# PLCC-RP2350B.net
KiCad netlist of a schematic drawn in Altium Designer
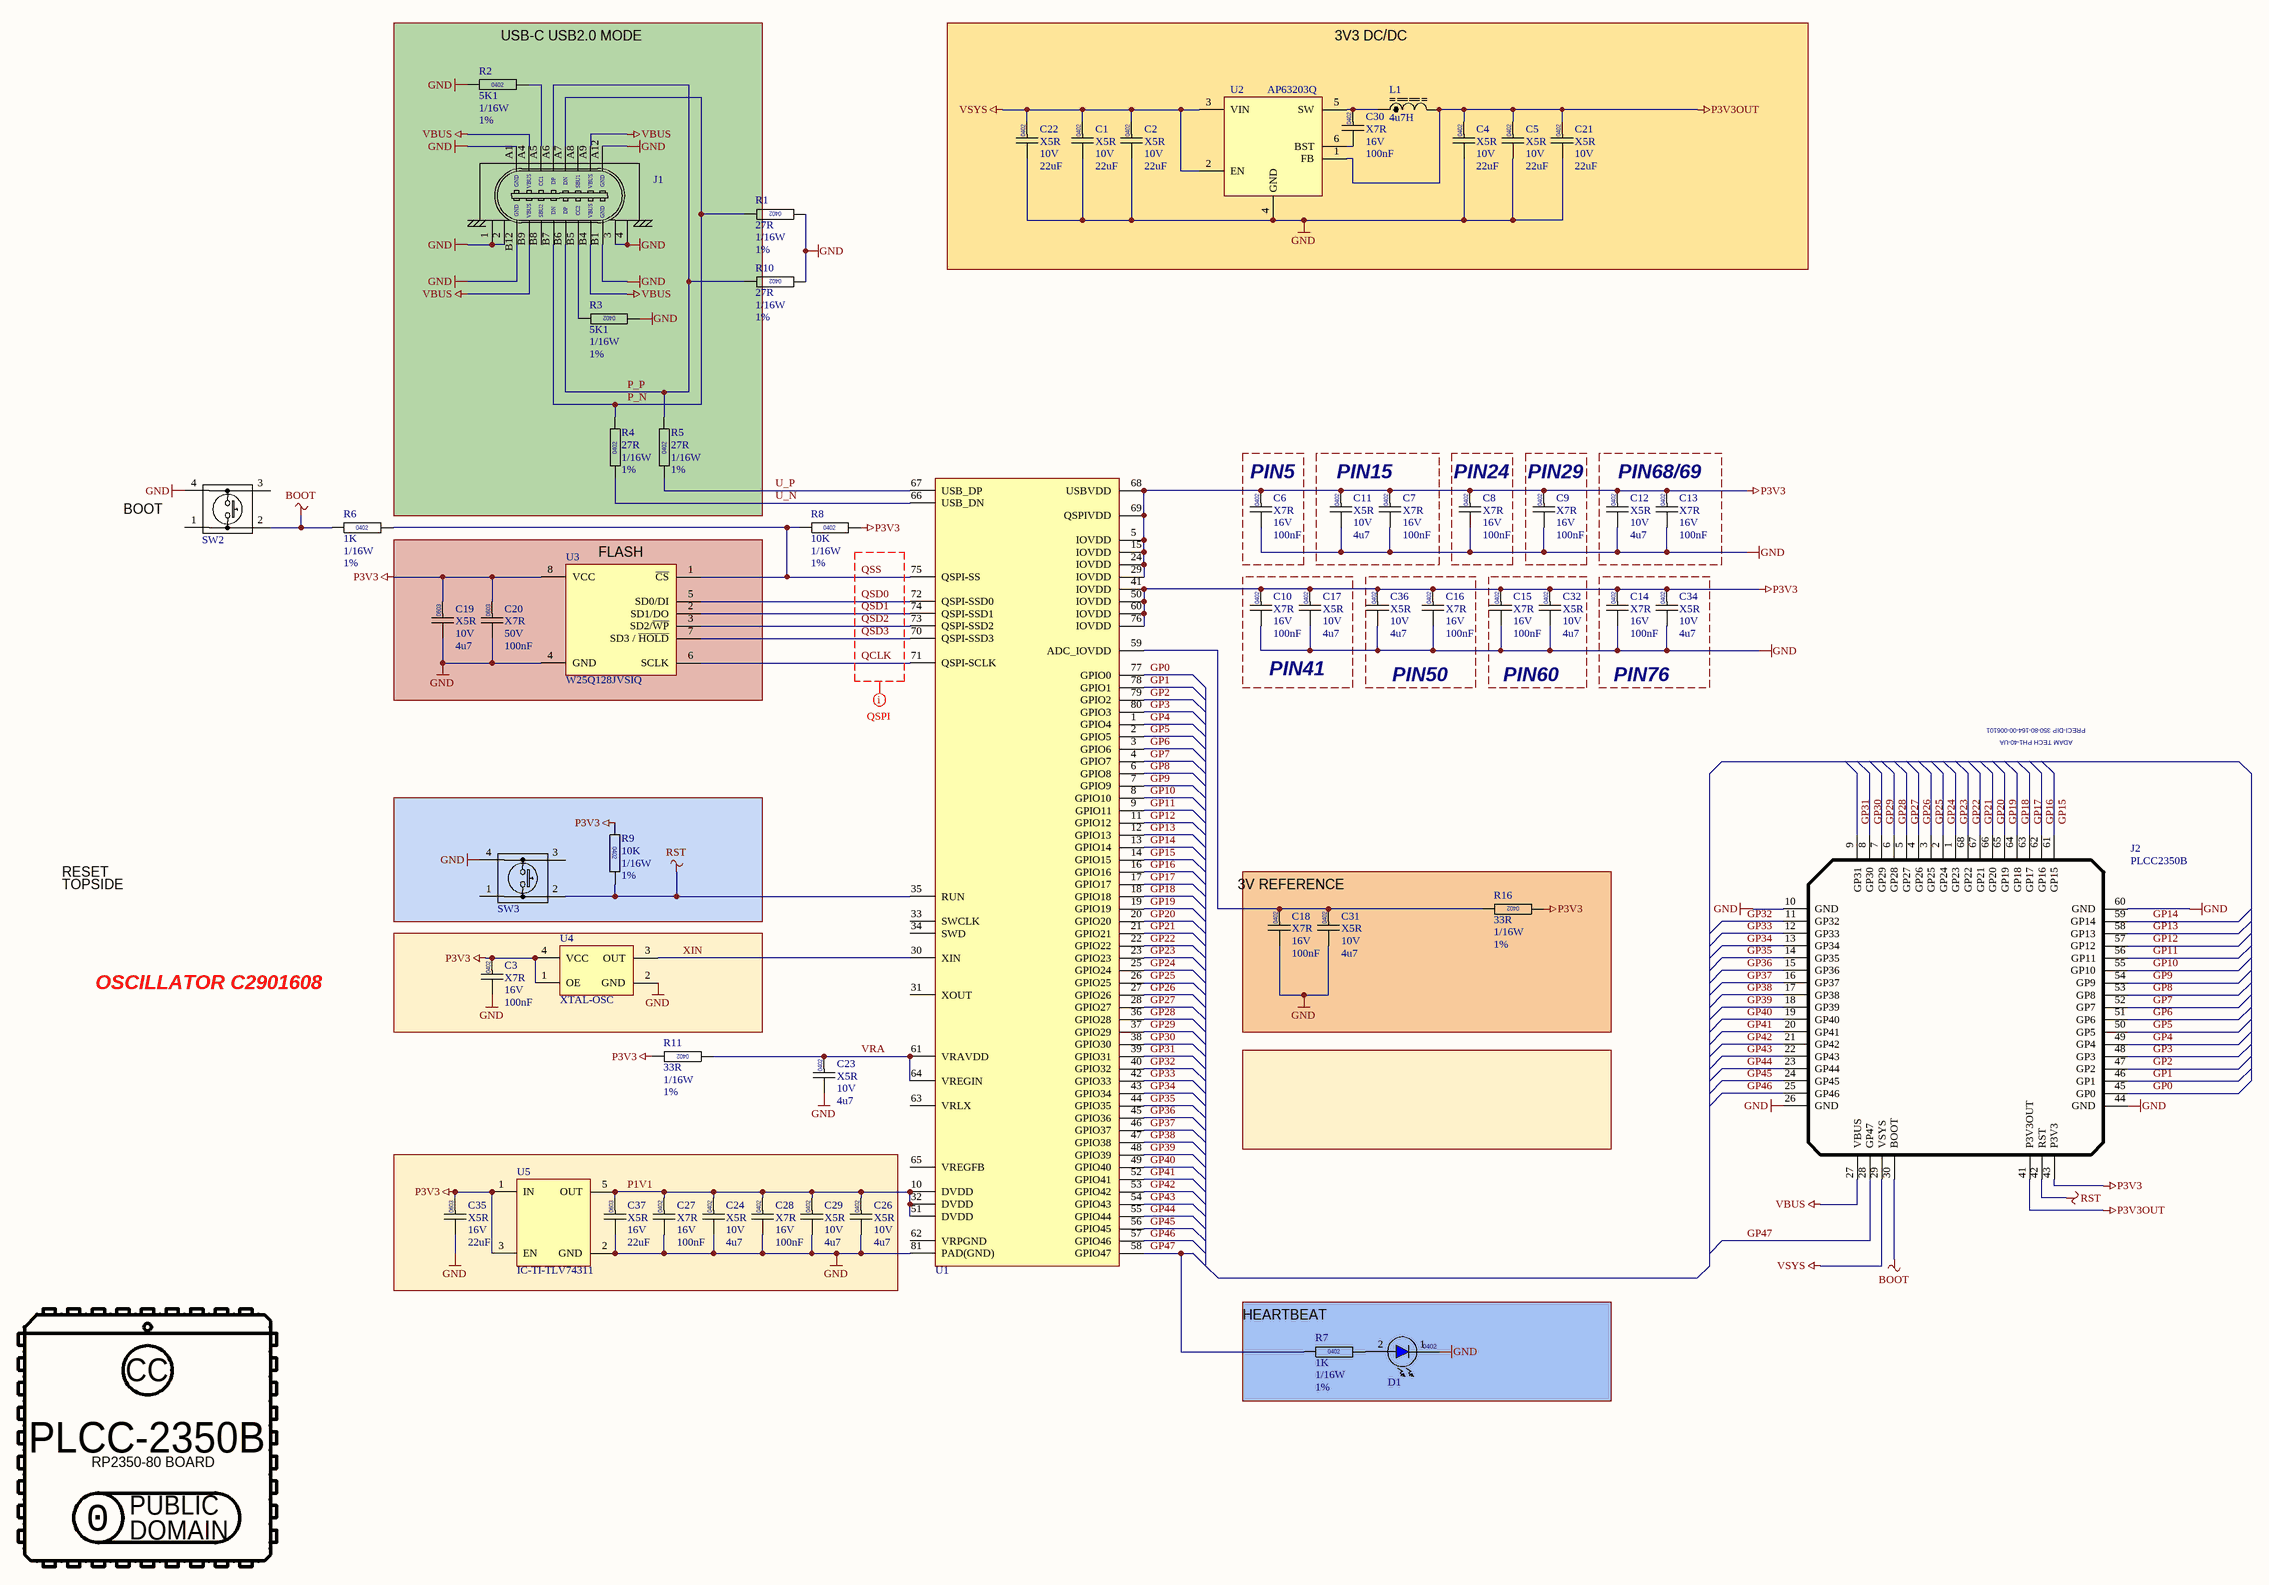
[diagram p0: PLCC-RP2350B.SchDoc]

(export (version "E")
  (design (tool "Eeschema 10.0.6"))
  (components
    (comp (ref "C1")
      (value "CAP0402")
      (footprint "CAPC0402")
      (description "CAPACITOR,CERAMIC,22uF,10V,X5R,0402")
      (fields
        (field (name "DIELECTRIC") "X5R")
        (field (name "VOLTAGE") "10V")
        (field (name "CAPACITANCE") "22uF")
      )
      (libsource (lib "CAPACITORS") (part "CAPC-0402-22uF-10V-X5R"))
    )
    (comp (ref "C2")
      (value "CAP0402")
      (footprint "CAPC0402")
      (description "CAPACITOR,CERAMIC,22uF,10V,X5R,0402")
      (fields
        (field (name "DIELECTRIC") "X5R")
        (field (name "VOLTAGE") "10V")
        (field (name "CAPACITANCE") "22uF")
      )
      (libsource (lib "CAPACITORS") (part "CAPC-0402-22uF-10V-X5R"))
    )
    (comp (ref "C3")
      (value "CAP0402")
      (footprint "CAPC0402")
      (description "CAPACITOR,CERAMIC,100nF,16V,X7R,0402")
      (fields
        (field (name "DIELECTRIC") "X7R")
        (field (name "VOLTAGE") "16V")
        (field (name "CAPACITANCE") "100nF")
      )
      (libsource (lib "CAPACITORS") (part "CAPC-0402-100nF-16V-X7R"))
    )
    (comp (ref "C4")
      (value "CAP0402")
      (footprint "CAPC0402")
      (description "CAPACITOR,CERAMIC,22uF,10V,X5R,0402")
      (fields
        (field (name "DIELECTRIC") "X5R")
        (field (name "VOLTAGE") "10V")
        (field (name "CAPACITANCE") "22uF")
      )
      (libsource (lib "CAPACITORS") (part "CAPC-0402-22uF-10V-X5R"))
    )
    (comp (ref "C5")
      (value "CAP0402")
      (footprint "CAPC0402")
      (description "CAPACITOR,CERAMIC,22uF,10V,X5R,0402")
      (fields
        (field (name "DIELECTRIC") "X5R")
        (field (name "VOLTAGE") "10V")
        (field (name "CAPACITANCE") "22uF")
      )
      (libsource (lib "CAPACITORS") (part "CAPC-0402-22uF-10V-X5R"))
    )
    (comp (ref "C6")
      (value "CAP0402")
      (footprint "CAPC0402")
      (description "CAPACITOR,CERAMIC,100nF,16V,X7R,0402")
      (fields
        (field (name "DIELECTRIC") "X7R")
        (field (name "VOLTAGE") "16V")
        (field (name "CAPACITANCE") "100nF")
      )
      (libsource (lib "CAPACITORS") (part "CAPC-0402-100nF-16V-X7R"))
    )
    (comp (ref "C7")
      (value "CAP0402")
      (footprint "CAPC0402")
      (description "CAPACITOR,CERAMIC,100nF,16V,X7R,0402")
      (fields
        (field (name "DIELECTRIC") "X7R")
        (field (name "VOLTAGE") "16V")
        (field (name "CAPACITANCE") "100nF")
      )
      (libsource (lib "CAPACITORS") (part "CAPC-0402-100nF-16V-X7R"))
    )
    (comp (ref "C8")
      (value "CAP0402")
      (footprint "CAPC0402")
      (description "CAPACITOR,CERAMIC,100nF,16V,X7R,0402")
      (fields
        (field (name "DIELECTRIC") "X7R")
        (field (name "VOLTAGE") "16V")
        (field (name "CAPACITANCE") "100nF")
      )
      (libsource (lib "CAPACITORS") (part "CAPC-0402-100nF-16V-X7R"))
    )
    (comp (ref "C9")
      (value "CAP0402")
      (footprint "CAPC0402")
      (description "CAPACITOR,CERAMIC,100nF,16V,X7R,0402")
      (fields
        (field (name "DIELECTRIC") "X7R")
        (field (name "VOLTAGE") "16V")
        (field (name "CAPACITANCE") "100nF")
      )
      (libsource (lib "CAPACITORS") (part "CAPC-0402-100nF-16V-X7R"))
    )
    (comp (ref "C10")
      (value "CAP0402")
      (footprint "CAPC0402")
      (description "CAPACITOR,CERAMIC,100nF,16V,X7R,0402")
      (fields
        (field (name "DIELECTRIC") "X7R")
        (field (name "VOLTAGE") "16V")
        (field (name "CAPACITANCE") "100nF")
      )
      (libsource (lib "CAPACITORS") (part "CAPC-0402-100nF-16V-X7R"))
    )
    (comp (ref "C11")
      (value "CAP0402")
      (footprint "CAPC0402")
      (description "CAPACITOR,CERAMIC,4u7,10V,X5R,0402")
      (fields
        (field (name "DIELECTRIC") "X5R")
        (field (name "VOLTAGE") "10V")
        (field (name "CAPACITANCE") "4u7")
      )
      (libsource (lib "CAPACITORS") (part "CAPC-0402-4u7-10V-X5R"))
    )
    (comp (ref "C12")
      (value "CAP0402")
      (footprint "CAPC0402")
      (description "CAPACITOR,CERAMIC,4u7,10V,X5R,0402")
      (fields
        (field (name "DIELECTRIC") "X5R")
        (field (name "VOLTAGE") "10V")
        (field (name "CAPACITANCE") "4u7")
      )
      (libsource (lib "CAPACITORS") (part "CAPC-0402-4u7-10V-X5R"))
    )
    (comp (ref "C13")
      (value "CAP0402")
      (footprint "CAPC0402")
      (description "CAPACITOR,CERAMIC,100nF,16V,X7R,0402")
      (fields
        (field (name "DIELECTRIC") "X7R")
        (field (name "VOLTAGE") "16V")
        (field (name "CAPACITANCE") "100nF")
      )
      (libsource (lib "CAPACITORS") (part "CAPC-0402-100nF-16V-X7R"))
    )
    (comp (ref "C14")
      (value "CAP0402")
      (footprint "CAPC0402")
      (description "CAPACITOR,CERAMIC,100nF,16V,X7R,0402")
      (fields
        (field (name "DIELECTRIC") "X7R")
        (field (name "VOLTAGE") "16V")
        (field (name "CAPACITANCE") "100nF")
      )
      (libsource (lib "CAPACITORS") (part "CAPC-0402-100nF-16V-X7R"))
    )
    (comp (ref "C15")
      (value "CAP0402")
      (footprint "CAPC0402")
      (description "CAPACITOR,CERAMIC,100nF,16V,X7R,0402")
      (fields
        (field (name "DIELECTRIC") "X7R")
        (field (name "VOLTAGE") "16V")
        (field (name "CAPACITANCE") "100nF")
      )
      (libsource (lib "CAPACITORS") (part "CAPC-0402-100nF-16V-X7R"))
    )
    (comp (ref "C16")
      (value "CAP0402")
      (footprint "CAPC0402")
      (description "CAPACITOR,CERAMIC,100nF,16V,X7R,0402")
      (fields
        (field (name "DIELECTRIC") "X7R")
        (field (name "VOLTAGE") "16V")
        (field (name "CAPACITANCE") "100nF")
      )
      (libsource (lib "CAPACITORS") (part "CAPC-0402-100nF-16V-X7R"))
    )
    (comp (ref "C17")
      (value "CAP0402")
      (footprint "CAPC0402")
      (description "CAPACITOR,CERAMIC,4u7,10V,X5R,0402")
      (fields
        (field (name "DIELECTRIC") "X5R")
        (field (name "VOLTAGE") "10V")
        (field (name "CAPACITANCE") "4u7")
      )
      (libsource (lib "CAPACITORS") (part "CAPC-0402-4u7-10V-X5R"))
    )
    (comp (ref "C18")
      (value "CAP0402")
      (footprint "CAPC0402")
      (description "CAPACITOR,CERAMIC,100nF,16V,X7R,0402")
      (fields
        (field (name "DIELECTRIC") "X7R")
        (field (name "VOLTAGE") "16V")
        (field (name "CAPACITANCE") "100nF")
      )
      (libsource (lib "CAPACITORS") (part "CAPC-0402-100nF-16V-X7R"))
    )
    (comp (ref "C19")
      (value "CAP0603")
      (footprint "CAPC0603")
      (description "CAPACITOR,CERAMIC,4u7,10V,X5R,0603")
      (fields
        (field (name "DIELECTRIC") "X5R")
        (field (name "VOLTAGE") "10V")
        (field (name "CAPACITANCE") "4u7")
      )
      (libsource (lib "CAPACITORS") (part "CAPC-0603-4u7-10V-X5R"))
    )
    (comp (ref "C20")
      (value "CAP0603")
      (footprint "CAPC0603")
      (description "CAPACITOR,CERAMIC,100nF,50V,X7R,0603")
      (fields
        (field (name "DIELECTRIC") "X7R")
        (field (name "VOLTAGE") "50V")
        (field (name "CAPACITANCE") "100nF")
      )
      (libsource (lib "CAPACITORS") (part "CAPC-0603-100nF-50V-X7R"))
    )
    (comp (ref "C21")
      (value "CAP0402")
      (footprint "CAPC0402")
      (description "CAPACITOR,CERAMIC,22uF,10V,X5R,0402")
      (fields
        (field (name "DIELECTRIC") "X5R")
        (field (name "VOLTAGE") "10V")
        (field (name "CAPACITANCE") "22uF")
      )
      (libsource (lib "CAPACITORS") (part "CAPC-0402-22uF-10V-X5R"))
    )
    (comp (ref "C22")
      (value "CAP0402")
      (footprint "CAPC0402")
      (description "CAPACITOR,CERAMIC,22uF,10V,X5R,0402")
      (fields
        (field (name "DIELECTRIC") "X5R")
        (field (name "VOLTAGE") "10V")
        (field (name "CAPACITANCE") "22uF")
      )
      (libsource (lib "CAPACITORS") (part "CAPC-0402-22uF-10V-X5R"))
    )
    (comp (ref "C23")
      (value "CAP0402")
      (footprint "CAPC0402")
      (description "CAPACITOR,CERAMIC,4u7,10V,X5R,0402")
      (fields
        (field (name "DIELECTRIC") "X5R")
        (field (name "VOLTAGE") "10V")
        (field (name "CAPACITANCE") "4u7")
      )
      (libsource (lib "CAPACITORS") (part "CAPC-0402-4u7-10V-X5R"))
    )
    (comp (ref "C24")
      (value "CAP0402")
      (footprint "CAPC0402")
      (description "CAPACITOR,CERAMIC,4u7,10V,X5R,0402")
      (fields
        (field (name "DIELECTRIC") "X5R")
        (field (name "VOLTAGE") "10V")
        (field (name "CAPACITANCE") "4u7")
      )
      (libsource (lib "CAPACITORS") (part "CAPC-0402-4u7-10V-X5R"))
    )
    (comp (ref "C26")
      (value "CAP0402")
      (footprint "CAPC0402")
      (description "CAPACITOR,CERAMIC,4u7,10V,X5R,0402")
      (fields
        (field (name "DIELECTRIC") "X5R")
        (field (name "VOLTAGE") "10V")
        (field (name "CAPACITANCE") "4u7")
      )
      (libsource (lib "CAPACITORS") (part "CAPC-0402-4u7-10V-X5R"))
    )
    (comp (ref "C27")
      (value "CAP0402")
      (footprint "CAPC0402")
      (description "CAPACITOR,CERAMIC,100nF,16V,X7R,0402")
      (fields
        (field (name "DIELECTRIC") "X7R")
        (field (name "VOLTAGE") "16V")
        (field (name "CAPACITANCE") "100nF")
      )
      (libsource (lib "CAPACITORS") (part "CAPC-0402-100nF-16V-X7R"))
    )
    (comp (ref "C28")
      (value "CAP0402")
      (footprint "CAPC0402")
      (description "CAPACITOR,CERAMIC,100nF,16V,X7R,0402")
      (fields
        (field (name "DIELECTRIC") "X7R")
        (field (name "VOLTAGE") "16V")
        (field (name "CAPACITANCE") "100nF")
      )
      (libsource (lib "CAPACITORS") (part "CAPC-0402-100nF-16V-X7R"))
    )
    (comp (ref "C29")
      (value "CAP0402")
      (footprint "CAPC0402")
      (description "CAPACITOR,CERAMIC,4u7,10V,X5R,0402")
      (fields
        (field (name "DIELECTRIC") "X5R")
        (field (name "VOLTAGE") "10V")
        (field (name "CAPACITANCE") "4u7")
      )
      (libsource (lib "CAPACITORS") (part "CAPC-0402-4u7-10V-X5R"))
    )
    (comp (ref "C30")
      (value "CAP0402")
      (footprint "CAPC0402")
      (description "CAPACITOR,CERAMIC,100nF,16V,X7R,0402")
      (fields
        (field (name "DIELECTRIC") "X7R")
        (field (name "VOLTAGE") "16V")
        (field (name "CAPACITANCE") "100nF")
      )
      (libsource (lib "CAPACITORS") (part "CAPC-0402-100nF-16V-X7R"))
    )
    (comp (ref "C31")
      (value "CAP0402")
      (footprint "CAPC0402")
      (description "CAPACITOR,CERAMIC,4u7,10V,X5R,0402")
      (fields
        (field (name "DIELECTRIC") "X5R")
        (field (name "VOLTAGE") "10V")
        (field (name "CAPACITANCE") "4u7")
      )
      (libsource (lib "CAPACITORS") (part "CAPC-0402-4u7-10V-X5R"))
    )
    (comp (ref "C32")
      (value "CAP0402")
      (footprint "CAPC0402")
      (description "CAPACITOR,CERAMIC,4u7,10V,X5R,0402")
      (fields
        (field (name "DIELECTRIC") "X5R")
        (field (name "VOLTAGE") "10V")
        (field (name "CAPACITANCE") "4u7")
      )
      (libsource (lib "CAPACITORS") (part "CAPC-0402-4u7-10V-X5R"))
    )
    (comp (ref "C34")
      (value "CAP0402")
      (footprint "CAPC0402")
      (description "CAPACITOR,CERAMIC,4u7,10V,X5R,0402")
      (fields
        (field (name "DIELECTRIC") "X5R")
        (field (name "VOLTAGE") "10V")
        (field (name "CAPACITANCE") "4u7")
      )
      (libsource (lib "CAPACITORS") (part "CAPC-0402-4u7-10V-X5R"))
    )
    (comp (ref "C35")
      (value "CAP0603")
      (footprint "CAPC0603")
      (description "CAPACITOR,CERAMIC,22uF,16V,X5R,0603")
      (fields
        (field (name "DIELECTRIC") "X5R")
        (field (name "VOLTAGE") "16V")
        (field (name "CAPACITANCE") "22uF")
      )
      (libsource (lib "CAPACITORS") (part "CAPC-0603-22uF-16V-X5R"))
    )
    (comp (ref "C36")
      (value "CAP0402")
      (footprint "CAPC0402")
      (description "CAPACITOR,CERAMIC,4u7,10V,X5R,0402")
      (fields
        (field (name "DIELECTRIC") "X5R")
        (field (name "VOLTAGE") "10V")
        (field (name "CAPACITANCE") "4u7")
      )
      (libsource (lib "CAPACITORS") (part "CAPC-0402-4u7-10V-X5R"))
    )
    (comp (ref "C37")
      (value "CAP0603")
      (footprint "CAPC0603")
      (description "CAPACITOR,CERAMIC,22uF,16V,X5R,0603")
      (fields
        (field (name "DIELECTRIC") "X5R")
        (field (name "VOLTAGE") "16V")
        (field (name "CAPACITANCE") "22uF")
      )
      (libsource (lib "CAPACITORS") (part "CAPC-0603-22uF-16V-X5R"))
    )
    (comp (ref "D1")
      (value "LED-0402-BLUE")
      (footprint "LED-0402-BLUE")
      (description "LED,SMD,BLUE,90mCd,0603")
      (libsource (lib "LED") (part "LED-0402-BLUE"))
    )
    (comp (ref "J1")
      (value "CONN-USBC-USB2-HOR")
      (footprint "CONN-GCT-USB4085")
      (description "CONN,USB-C,16P,RA,TH,8.94X9.17")
      (libsource (lib "CONNECTORS") (part "CONN-USBC-USB2-HOR"))
    )
    (comp (ref "J2")
      (value "PLCC2350B")
      (footprint "PLCC2350B")
      (libsource (lib "PLCC-RP2350B") (part "PLCC2350B"))
    )
    (comp (ref "L1")
      (value "4u7H")
      (footprint "IND-ABRACON-ASPI-3012S-3R9N-T")
      (description "IND,4.7uH,1.06A,3X3, NRH3012T4R7MN")
      (fields (field (name "Comment") "4.7uH"))
      (libsource (lib "INDUCTORS") (part "IND-TAIYO-NRH3012T4R7MN"))
    )
    (comp (ref "LOGO1")
      (value "LOGO-LICENSE-CC0-PUBLIC")
      (footprint "LOGO-LICENSE-CC0-PUBLIC")
      (libsource (lib "LOGO") (part "LOGO-LICENSE-CC0-PUBLIC"))
    )
    (comp (ref "LOGO2")
      (value "LOGO-LICENSE-CC")
      (footprint "LOGO-LICENSE-CC")
      (libsource (lib "LOGO") (part "LOGO-LICENSE-CC"))
    )
    (comp (ref "R1")
      (value "27R")
      (footprint "RESC0402")
      (description "RESISTOR,27R,1%,63mW,0402 (1005)")
      (fields
        (field (name "POWER") "1/16W")
        (field (name "TOLERANCE") "1%")
        (field (name "Comment") "RESC0402")
      )
      (libsource (lib "RESISTORS") (part "RESC-0402-27R-1%-1/10W"))
    )
    (comp (ref "R2")
      (value "5K1")
      (footprint "RESC0402")
      (description "RESISTOR,5K1,1%,63mW,0402 (1005)")
      (fields
        (field (name "POWER") "1/16W")
        (field (name "TOLERANCE") "1%")
        (field (name "Comment") "RESC0402")
      )
      (libsource (lib "RESISTORS") (part "RESC-0402-5K1-1%-1/10W"))
    )
    (comp (ref "R3")
      (value "5K1")
      (footprint "RESC0402")
      (description "RESISTOR,5K1,1%,63mW,0402 (1005)")
      (fields
        (field (name "POWER") "1/16W")
        (field (name "TOLERANCE") "1%")
        (field (name "Comment") "RESC0402")
      )
      (libsource (lib "RESISTORS") (part "RESC-0402-5K1-1%-1/10W"))
    )
    (comp (ref "R4")
      (value "27R")
      (footprint "RESC0402")
      (description "RESISTOR,27R,1%,63mW,0402 (1005)")
      (fields
        (field (name "POWER") "1/16W")
        (field (name "TOLERANCE") "1%")
        (field (name "Comment") "RESC0402")
      )
      (libsource (lib "RESISTORS") (part "RESC-0402-27R-1%-1/10W"))
    )
    (comp (ref "R5")
      (value "27R")
      (footprint "RESC0402")
      (description "RESISTOR,27R,1%,63mW,0402 (1005)")
      (fields
        (field (name "POWER") "1/16W")
        (field (name "TOLERANCE") "1%")
        (field (name "Comment") "RESC0402")
      )
      (libsource (lib "RESISTORS") (part "RESC-0402-27R-1%-1/10W"))
    )
    (comp (ref "R6")
      (value "1K")
      (footprint "RESC0402")
      (description "RESISTOR,1K,1%,63mW,0402 (1005)")
      (fields
        (field (name "POWER") "1/16W")
        (field (name "TOLERANCE") "1%")
        (field (name "Comment") "RESC0402")
      )
      (libsource (lib "RESISTORS") (part "RESC-0402-1K-1%-1/10W"))
    )
    (comp (ref "R7")
      (value "1K")
      (footprint "RESC0402")
      (description "RESISTOR,1K,1%,63mW,0402 (1005)")
      (fields
        (field (name "POWER") "1/16W")
        (field (name "TOLERANCE") "1%")
        (field (name "Comment") "RESC0402")
      )
      (libsource (lib "RESISTORS") (part "RESC-0402-1K-1%-1/10W"))
    )
    (comp (ref "R8")
      (value "10K")
      (footprint "RESC0402")
      (description "RESISTOR,10K,1%,63mW,0402 (1005)")
      (fields
        (field (name "POWER") "1/16W")
        (field (name "TOLERANCE") "1%")
        (field (name "Comment") "RESC0402")
      )
      (libsource (lib "RESISTORS") (part "RESC-0402-10K-1%-1/10W"))
    )
    (comp (ref "R9")
      (value "10K")
      (footprint "RESC0402")
      (description "RESISTOR,10K,1%,63mW,0402 (1005)")
      (fields
        (field (name "POWER") "1/16W")
        (field (name "TOLERANCE") "1%")
        (field (name "Comment") "RESC0402")
      )
      (libsource (lib "RESISTORS") (part "RESC-0402-10K-1%-1/10W"))
    )
    (comp (ref "R10")
      (value "27R")
      (footprint "RESC0402")
      (description "RESISTOR,27R,1%,63mW,0402 (1005)")
      (fields
        (field (name "POWER") "1/16W")
        (field (name "TOLERANCE") "1%")
        (field (name "Comment") "RESC0402")
      )
      (libsource (lib "RESISTORS") (part "RESC-0402-27R-1%-1/10W"))
    )
    (comp (ref "R11")
      (value "33R")
      (footprint "RESC0402")
      (description "RESISTOR,33R,1%,63mW,0402 (1005)")
      (fields
        (field (name "POWER") "1/16W")
        (field (name "TOLERANCE") "1%")
        (field (name "Comment") "RESC0402")
      )
      (libsource (lib "RESISTORS") (part "RESC-0402-33R-1%-1/10W"))
    )
    (comp (ref "R16")
      (value "33R")
      (footprint "RESC0402")
      (description "RESISTOR,33R,1%,63mW,0402 (1005)")
      (fields
        (field (name "POWER") "1/16W")
        (field (name "TOLERANCE") "1%")
        (field (name "Comment") "RESC0402")
      )
      (libsource (lib "RESISTORS") (part "RESC-0402-33R-1%-1/10W"))
    )
    (comp (ref "SW2")
      (value "SWITCH-PANASONIC-EVP-AA202K")
      (footprint "SWITCH-PANASONIC-EVP-AA202K")
      (description "SW,SMD,TACT,4PIN,2.9X3.5,4PIN")
      (libsource (lib "SWITCH") (part "SWITCH-PANASONIC-EVP-AA202K"))
    )
    (comp (ref "SW3")
      (value "SWITCH-PANASONIC-EVP-AA202K")
      (footprint "SWITCH-PANASONIC-EVP-AA202K")
      (description "SW,SMD,TACT,4PIN,2.9X3.5,4PIN")
      (libsource (lib "SWITCH") (part "SWITCH-PANASONIC-EVP-AA202K"))
    )
    (comp (ref "U1")
      (value "IC-RP2350-DIP64")
      (footprint "QFN40P1000X1000X90_HS-81N")
      (description "IC,CPU,RP2350B,QFN80")
      (libsource (lib "IC-CPU") (part "IC-RP2350-DIP64"))
    )
    (comp (ref "U2")
      (value "AP63203Q")
      (footprint "SOT23-6")
      (description "IC,PMIC,STEP-DOWN, 2A 3.3V")
      (libsource (lib "IC-REG") (part "IC-DIODES-AP63203Q"))
    )
    (comp (ref "U3")
      (value "W25Q128JVSIQ")
      (footprint "SO127P790-8N")
      (description "IC,FLASH,QSPI,16Mx8")
      (libsource (lib "IC-SPI") (part "IC-WINBOND-W25Q128JVSIQ"))
    )
    (comp (ref "U4")
      (value "XTAL-OSC")
      (footprint "XOSC-SCTF-SX1M12.000M10F30TNN")
      (libsource (lib "PLCC-RP2350B") (part "XTAL-OSC"))
    )
    (comp (ref "U5")
      (value "IC-TI-TLV74311")
      (footprint "SOT23-5")
      (libsource (lib "PLCC-RP2350B") (part "IC-TI-TLV74311"))
    )
  )
  (nets
    (net (code "1") (name "/GP0") (class "Default")
      (node (ref "J2") (pin "45") (pinfunction "GP0_45") (pintype "passive"))
      (node (ref "U1") (pin "77") (pinfunction "GPIO0_77") (pintype "passive"))
    )
    (net (code "2") (name "/GP1") (class "Default")
      (node (ref "J2") (pin "46") (pinfunction "GP1_46") (pintype "passive"))
      (node (ref "U1") (pin "78") (pinfunction "GPIO1_78") (pintype "passive"))
    )
    (net (code "3") (name "/GP2") (class "Default")
      (node (ref "J2") (pin "47") (pinfunction "GP2_47") (pintype "passive"))
      (node (ref "U1") (pin "79") (pinfunction "GPIO2_79") (pintype "passive"))
    )
    (net (code "4") (name "/GP3") (class "Default")
      (node (ref "J2") (pin "48") (pinfunction "GP3_48") (pintype "passive"))
      (node (ref "U1") (pin "80") (pinfunction "GPIO3_80") (pintype "passive"))
    )
    (net (code "5") (name "/GP4") (class "Default")
      (node (ref "J2") (pin "49") (pinfunction "GP4_49") (pintype "passive"))
      (node (ref "U1") (pin "1") (pinfunction "GPIO4_1") (pintype "passive"))
    )
    (net (code "6") (name "/GP5") (class "Default")
      (node (ref "J2") (pin "50") (pinfunction "GP5_50") (pintype "passive"))
      (node (ref "U1") (pin "2") (pinfunction "GPIO5_2") (pintype "passive"))
    )
    (net (code "7") (name "/GP6") (class "Default")
      (node (ref "J2") (pin "51") (pinfunction "GP6_51") (pintype "passive"))
      (node (ref "U1") (pin "3") (pinfunction "GPIO6_3") (pintype "passive"))
    )
    (net (code "8") (name "/GP7") (class "Default")
      (node (ref "J2") (pin "52") (pinfunction "GP7_52") (pintype "passive"))
      (node (ref "U1") (pin "4") (pinfunction "GPIO7_4") (pintype "passive"))
    )
    (net (code "9") (name "/GP8") (class "Default")
      (node (ref "J2") (pin "53") (pinfunction "GP8_53") (pintype "passive"))
      (node (ref "U1") (pin "6") (pinfunction "GPIO8_6") (pintype "passive"))
    )
    (net (code "10") (name "/GP9") (class "Default")
      (node (ref "J2") (pin "54") (pinfunction "GP9_54") (pintype "passive"))
      (node (ref "U1") (pin "7") (pinfunction "GPIO9_7") (pintype "passive"))
    )
    (net (code "11") (name "/GP10") (class "Default")
      (node (ref "J2") (pin "55") (pinfunction "GP10_55") (pintype "passive"))
      (node (ref "U1") (pin "8") (pinfunction "GPIO10_8") (pintype "passive"))
    )
    (net (code "12") (name "/GP11") (class "Default")
      (node (ref "J2") (pin "56") (pinfunction "GP11_56") (pintype "passive"))
      (node (ref "U1") (pin "9") (pinfunction "GPIO11_9") (pintype "passive"))
    )
    (net (code "13") (name "/GP12") (class "Default")
      (node (ref "J2") (pin "57") (pinfunction "GP12_57") (pintype "passive"))
      (node (ref "U1") (pin "11") (pinfunction "GPIO12_11") (pintype "passive"))
    )
    (net (code "14") (name "/GP13") (class "Default")
      (node (ref "J2") (pin "58") (pinfunction "GP13_58") (pintype "passive"))
      (node (ref "U1") (pin "12") (pinfunction "GPIO13_12") (pintype "passive"))
    )
    (net (code "15") (name "/GP14") (class "Default")
      (node (ref "J2") (pin "59") (pinfunction "GP14_59") (pintype "passive"))
      (node (ref "U1") (pin "13") (pinfunction "GPIO14_13") (pintype "passive"))
    )
    (net (code "16") (name "/GP15") (class "Default")
      (node (ref "J2") (pin "61") (pinfunction "GP15_61") (pintype "passive"))
      (node (ref "U1") (pin "14") (pinfunction "GPIO15_14") (pintype "passive"))
    )
    (net (code "17") (name "/GP16") (class "Default")
      (node (ref "J2") (pin "62") (pinfunction "GP16_62") (pintype "passive"))
      (node (ref "U1") (pin "16") (pinfunction "GPIO16_16") (pintype "passive"))
    )
    (net (code "18") (name "/GP17") (class "Default")
      (node (ref "J2") (pin "63") (pinfunction "GP17_63") (pintype "passive"))
      (node (ref "U1") (pin "17") (pinfunction "GPIO17_17") (pintype "passive"))
    )
    (net (code "19") (name "/GP18") (class "Default")
      (node (ref "J2") (pin "64") (pinfunction "GP18_64") (pintype "passive"))
      (node (ref "U1") (pin "18") (pinfunction "GPIO18_18") (pintype "passive"))
    )
    (net (code "20") (name "/GP19") (class "Default")
      (node (ref "J2") (pin "65") (pinfunction "GP19_65") (pintype "passive"))
      (node (ref "U1") (pin "19") (pinfunction "GPIO19_19") (pintype "passive"))
    )
    (net (code "21") (name "/GP20") (class "Default")
      (node (ref "J2") (pin "66") (pinfunction "GP20_66") (pintype "passive"))
      (node (ref "U1") (pin "20") (pinfunction "GPIO20_20") (pintype "passive"))
    )
    (net (code "22") (name "/GP21") (class "Default")
      (node (ref "J2") (pin "67") (pinfunction "GP21_67") (pintype "passive"))
      (node (ref "U1") (pin "21") (pinfunction "GPIO21_21") (pintype "passive"))
    )
    (net (code "23") (name "/GP22") (class "Default")
      (node (ref "J2") (pin "68") (pinfunction "GP22_68") (pintype "passive"))
      (node (ref "U1") (pin "22") (pinfunction "GPIO22_22") (pintype "passive"))
    )
    (net (code "24") (name "/GP23") (class "Default")
      (node (ref "J2") (pin "1") (pinfunction "GP23_1") (pintype "passive"))
      (node (ref "U1") (pin "23") (pinfunction "GPIO23_23") (pintype "passive"))
    )
    (net (code "25") (name "/GP24") (class "Default")
      (node (ref "J2") (pin "2") (pinfunction "GP24_2") (pintype "passive"))
      (node (ref "U1") (pin "25") (pinfunction "GPIO24_25") (pintype "passive"))
    )
    (net (code "26") (name "/GP25") (class "Default")
      (node (ref "J2") (pin "3") (pinfunction "GP25_3") (pintype "passive"))
      (node (ref "U1") (pin "26") (pinfunction "GPIO25_26") (pintype "passive"))
    )
    (net (code "27") (name "/GP26") (class "Default")
      (node (ref "J2") (pin "4") (pinfunction "GP26_4") (pintype "passive"))
      (node (ref "U1") (pin "27") (pinfunction "GPIO26_27") (pintype "passive"))
    )
    (net (code "28") (name "/GP27") (class "Default")
      (node (ref "J2") (pin "5") (pinfunction "GP27_5") (pintype "passive"))
      (node (ref "U1") (pin "28") (pinfunction "GPIO27_28") (pintype "passive"))
    )
    (net (code "29") (name "/GP28") (class "Default")
      (node (ref "J2") (pin "6") (pinfunction "GP28_6") (pintype "passive"))
      (node (ref "U1") (pin "36") (pinfunction "GPIO28_36") (pintype "passive"))
    )
    (net (code "30") (name "/GP29") (class "Default")
      (node (ref "J2") (pin "7") (pinfunction "GP29_7") (pintype "passive"))
      (node (ref "U1") (pin "37") (pinfunction "GPIO29_37") (pintype "passive"))
    )
    (net (code "31") (name "/GP30") (class "Default")
      (node (ref "J2") (pin "8") (pinfunction "GP30_8") (pintype "passive"))
      (node (ref "U1") (pin "38") (pinfunction "GPIO30_38") (pintype "passive"))
    )
    (net (code "32") (name "/GP31") (class "Default")
      (node (ref "J2") (pin "9") (pinfunction "GP31_9") (pintype "passive"))
      (node (ref "U1") (pin "39") (pinfunction "GPIO31_39") (pintype "passive"))
    )
    (net (code "33") (name "/GP32") (class "Default")
      (node (ref "J2") (pin "11") (pinfunction "GP32_11") (pintype "passive"))
      (node (ref "U1") (pin "40") (pinfunction "GPIO32_40") (pintype "passive"))
    )
    (net (code "34") (name "/GP33") (class "Default")
      (node (ref "J2") (pin "12") (pinfunction "GP33_12") (pintype "passive"))
      (node (ref "U1") (pin "42") (pinfunction "GPIO33_42") (pintype "passive"))
    )
    (net (code "35") (name "/GP34") (class "Default")
      (node (ref "J2") (pin "13") (pinfunction "GP34_13") (pintype "passive"))
      (node (ref "U1") (pin "43") (pinfunction "GPIO34_43") (pintype "passive"))
    )
    (net (code "36") (name "/GP35") (class "Default")
      (node (ref "J2") (pin "14") (pinfunction "GP35_14") (pintype "passive"))
      (node (ref "U1") (pin "44") (pinfunction "GPIO35_44") (pintype "passive"))
    )
    (net (code "37") (name "/GP36") (class "Default")
      (node (ref "J2") (pin "15") (pinfunction "GP36_15") (pintype "passive"))
      (node (ref "U1") (pin "45") (pinfunction "GPIO36_45") (pintype "passive"))
    )
    (net (code "38") (name "/GP37") (class "Default")
      (node (ref "J2") (pin "16") (pinfunction "GP37_16") (pintype "passive"))
      (node (ref "U1") (pin "46") (pinfunction "GPIO37_46") (pintype "passive"))
    )
    (net (code "39") (name "/GP38") (class "Default")
      (node (ref "J2") (pin "17") (pinfunction "GP38_17") (pintype "passive"))
      (node (ref "U1") (pin "47") (pinfunction "GPIO38_47") (pintype "passive"))
    )
    (net (code "40") (name "/GP39") (class "Default")
      (node (ref "J2") (pin "18") (pinfunction "GP39_18") (pintype "passive"))
      (node (ref "U1") (pin "48") (pinfunction "GPIO39_48") (pintype "passive"))
    )
    (net (code "41") (name "/GP40") (class "Default")
      (node (ref "J2") (pin "19") (pinfunction "GP40_19") (pintype "passive"))
      (node (ref "U1") (pin "49") (pinfunction "GPIO40_49") (pintype "passive"))
    )
    (net (code "42") (name "/GP41") (class "Default")
      (node (ref "J2") (pin "20") (pinfunction "GP41_20") (pintype "passive"))
      (node (ref "U1") (pin "52") (pinfunction "GPIO41_52") (pintype "passive"))
    )
    (net (code "43") (name "/GP42") (class "Default")
      (node (ref "J2") (pin "21") (pinfunction "GP42_21") (pintype "passive"))
      (node (ref "U1") (pin "53") (pinfunction "GPIO42_53") (pintype "passive"))
    )
    (net (code "44") (name "/GP43") (class "Default")
      (node (ref "J2") (pin "22") (pinfunction "GP43_22") (pintype "passive"))
      (node (ref "U1") (pin "54") (pinfunction "GPIO43_54") (pintype "passive"))
    )
    (net (code "45") (name "/GP44") (class "Default")
      (node (ref "J2") (pin "23") (pinfunction "GP44_23") (pintype "passive"))
      (node (ref "U1") (pin "55") (pinfunction "GPIO44_55") (pintype "passive"))
    )
    (net (code "46") (name "/GP45") (class "Default")
      (node (ref "J2") (pin "24") (pinfunction "GP45_24") (pintype "passive"))
      (node (ref "U1") (pin "56") (pinfunction "GPIO45_56") (pintype "passive"))
    )
    (net (code "47") (name "/GP46") (class "Default")
      (node (ref "J2") (pin "25") (pinfunction "GP46_25") (pintype "passive"))
      (node (ref "U1") (pin "57") (pinfunction "GPIO46_57") (pintype "passive"))
    )
    (net (code "48") (name "/GP47") (class "Default")
      (node (ref "J2") (pin "28") (pinfunction "GP47_28") (pintype "passive"))
      (node (ref "R7") (pin "1") (pintype "passive"))
      (node (ref "U1") (pin "58") (pinfunction "GPIO47_58") (pintype "passive"))
    )
    (net (code "49") (name "/P1V1") (class "Default")
      (node (ref "C24") (pin "1") (pintype "passive"))
      (node (ref "C26") (pin "1") (pintype "passive"))
      (node (ref "C27") (pin "1") (pintype "passive"))
      (node (ref "C28") (pin "1") (pintype "passive"))
      (node (ref "C29") (pin "1") (pintype "passive"))
      (node (ref "C37") (pin "1") (pintype "passive"))
      (node (ref "U1") (pin "10") (pinfunction "DVDD_10") (pintype "passive"))
      (node (ref "U1") (pin "32") (pinfunction "DVDD_32") (pintype "passive"))
      (node (ref "U1") (pin "51") (pinfunction "DVDD_51") (pintype "passive"))
      (node (ref "U5") (pin "5") (pinfunction "OUT_5") (pintype "passive"))
    )
    (net (code "50") (name "/P_N") (class "Default")
      (node (ref "J1") (pin "A7") (pinfunction "A7_A7") (pintype "passive"))
      (node (ref "J1") (pin "B7") (pinfunction "B7_B7") (pintype "passive"))
      (node (ref "R1") (pin "1") (pintype "passive"))
      (node (ref "R4") (pin "1") (pintype "passive"))
    )
    (net (code "51") (name "/P_P") (class "Default")
      (node (ref "J1") (pin "A6") (pinfunction "A6_A6") (pintype "passive"))
      (node (ref "J1") (pin "B6") (pinfunction "B6_B6") (pintype "passive"))
      (node (ref "R10") (pin "1") (pintype "passive"))
      (node (ref "R5") (pin "1") (pintype "passive"))
    )
    (net (code "52") (name "/QCLK") (class "Default")
      (node (ref "U1") (pin "71") (pinfunction "QSPI-SCLK_71") (pintype "passive"))
      (node (ref "U3") (pin "6") (pinfunction "SCLK_6") (pintype "passive"))
    )
    (net (code "53") (name "/QSD0") (class "Default")
      (node (ref "U1") (pin "72") (pinfunction "QSPI-SSD0_72") (pintype "passive"))
      (node (ref "U3") (pin "5") (pinfunction "SD0/DI_5") (pintype "passive"))
    )
    (net (code "54") (name "/QSD1") (class "Default")
      (node (ref "U1") (pin "74") (pinfunction "QSPI-SSD1_74") (pintype "passive"))
      (node (ref "U3") (pin "2") (pinfunction "SD1/DO_2") (pintype "passive"))
    )
    (net (code "55") (name "/QSD2") (class "Default")
      (node (ref "U1") (pin "73") (pinfunction "QSPI-SSD2_73") (pintype "passive"))
      (node (ref "U3") (pin "3") (pinfunction "SD2/~{WP}_3") (pintype "passive"))
    )
    (net (code "56") (name "/QSD3") (class "Default")
      (node (ref "U1") (pin "70") (pinfunction "QSPI-SSD3_70") (pintype "passive"))
      (node (ref "U3") (pin "7") (pinfunction "SD3_/_~{HOLD}_7") (pintype "passive"))
    )
    (net (code "57") (name "/QSS") (class "Default")
      (node (ref "R6") (pin "2") (pintype "passive"))
      (node (ref "R8") (pin "1") (pintype "passive"))
      (node (ref "U1") (pin "75") (pinfunction "QSPI-SS_75") (pintype "passive"))
      (node (ref "U3") (pin "1") (pinfunction "~{CS}_1") (pintype "passive"))
    )
    (net (code "58") (name "/U_N") (class "Default")
      (node (ref "R4") (pin "2") (pintype "passive"))
      (node (ref "U1") (pin "66") (pinfunction "USB_DN_66") (pintype "passive"))
    )
    (net (code "59") (name "/U_P") (class "Default")
      (node (ref "R5") (pin "2") (pintype "passive"))
      (node (ref "U1") (pin "67") (pinfunction "USB_DP_67") (pintype "passive"))
    )
    (net (code "60") (name "/VRA") (class "Default")
      (node (ref "C23") (pin "1") (pintype "passive"))
      (node (ref "R11") (pin "2") (pintype "passive"))
      (node (ref "U1") (pin "61") (pinfunction "VRAVDD_61") (pintype "passive"))
      (node (ref "U1") (pin "64") (pinfunction "VREGIN_64") (pintype "passive"))
    )
    (net (code "61") (name "/XIN") (class "Default")
      (node (ref "U1") (pin "30") (pinfunction "XIN_30") (pintype "passive"))
      (node (ref "U4") (pin "3") (pinfunction "OUT_3") (pintype "passive"))
    )
    (net (code "62") (name "BOOT") (class "Default")
      (node (ref "J2") (pin "30") (pinfunction "BOOT_30") (pintype "passive"))
      (node (ref "R6") (pin "1") (pintype "passive"))
      (node (ref "SW2") (pin "2") (pinfunction "2_2") (pintype "passive"))
    )
    (net (code "63") (name "GND") (class "Default")
      (node (ref "C1") (pin "2") (pintype "passive"))
      (node (ref "C10") (pin "2") (pintype "passive"))
      (node (ref "C11") (pin "2") (pintype "passive"))
      (node (ref "C12") (pin "2") (pintype "passive"))
      (node (ref "C13") (pin "2") (pintype "passive"))
      (node (ref "C14") (pin "2") (pintype "passive"))
      (node (ref "C15") (pin "2") (pintype "passive"))
      (node (ref "C16") (pin "2") (pintype "passive"))
      (node (ref "C17") (pin "2") (pintype "passive"))
      (node (ref "C18") (pin "2") (pintype "passive"))
      (node (ref "C19") (pin "2") (pintype "passive"))
      (node (ref "C2") (pin "2") (pintype "passive"))
      (node (ref "C20") (pin "2") (pintype "passive"))
      (node (ref "C21") (pin "2") (pintype "passive"))
      (node (ref "C22") (pin "2") (pintype "passive"))
      (node (ref "C23") (pin "2") (pintype "passive"))
      (node (ref "C24") (pin "2") (pintype "passive"))
      (node (ref "C26") (pin "2") (pintype "passive"))
      (node (ref "C27") (pin "2") (pintype "passive"))
      (node (ref "C28") (pin "2") (pintype "passive"))
      (node (ref "C29") (pin "2") (pintype "passive"))
      (node (ref "C3") (pin "2") (pintype "passive"))
      (node (ref "C31") (pin "2") (pintype "passive"))
      (node (ref "C32") (pin "2") (pintype "passive"))
      (node (ref "C34") (pin "2") (pintype "passive"))
      (node (ref "C35") (pin "2") (pintype "passive"))
      (node (ref "C36") (pin "2") (pintype "passive"))
      (node (ref "C37") (pin "2") (pintype "passive"))
      (node (ref "C4") (pin "2") (pintype "passive"))
      (node (ref "C5") (pin "2") (pintype "passive"))
      (node (ref "C6") (pin "2") (pintype "passive"))
      (node (ref "C7") (pin "2") (pintype "passive"))
      (node (ref "C8") (pin "2") (pintype "passive"))
      (node (ref "C9") (pin "2") (pintype "passive"))
      (node (ref "D1") (pin "1") (pinfunction "A_1") (pintype "passive"))
      (node (ref "J1") (pin "1") (pinfunction "1_1") (pintype "passive"))
      (node (ref "J1") (pin "2") (pinfunction "2_2") (pintype "passive"))
      (node (ref "J1") (pin "3") (pinfunction "3_3") (pintype "passive"))
      (node (ref "J1") (pin "4") (pinfunction "4_4") (pintype "passive"))
      (node (ref "J1") (pin "A1") (pinfunction "A1_A1") (pintype "passive"))
      (node (ref "J1") (pin "A12") (pinfunction "A12_A12") (pintype "passive"))
      (node (ref "J1") (pin "B1") (pinfunction "B1_B1") (pintype "passive"))
      (node (ref "J1") (pin "B12") (pinfunction "B12_B12") (pintype "passive"))
      (node (ref "J2") (pin "10") (pinfunction "GND_10") (pintype "passive"))
      (node (ref "J2") (pin "26") (pinfunction "GND_26") (pintype "passive"))
      (node (ref "J2") (pin "44") (pinfunction "GND_44") (pintype "passive"))
      (node (ref "J2") (pin "60") (pinfunction "GND_60") (pintype "passive"))
      (node (ref "R1") (pin "2") (pintype "passive"))
      (node (ref "R10") (pin "2") (pintype "passive"))
      (node (ref "R2") (pin "2") (pintype "passive"))
      (node (ref "R3") (pin "2") (pintype "passive"))
      (node (ref "SW2") (pin "4") (pinfunction "4_4") (pintype "passive"))
      (node (ref "SW3") (pin "4") (pinfunction "4_4") (pintype "passive"))
      (node (ref "U1") (pin "81") (pinfunction "PAD(GND)_81") (pintype "passive"))
      (node (ref "U2") (pin "4") (pinfunction "GND_4") (pintype "passive"))
      (node (ref "U3") (pin "4") (pinfunction "GND_4") (pintype "passive"))
      (node (ref "U4") (pin "2") (pinfunction "GND_2") (pintype "passive"))
      (node (ref "U5") (pin "2") (pinfunction "GND_2") (pintype "passive"))
    )
    (net (code "64") (name "Net-(D1-K)") (class "Default")
      (node (ref "D1") (pin "2") (pinfunction "K_2") (pintype "passive"))
      (node (ref "R7") (pin "2") (pintype "passive"))
    )
    (net (code "65") (name "Net-(J1-PadA5)") (class "Default")
      (node (ref "J1") (pin "A5") (pinfunction "A5_A5") (pintype "passive"))
      (node (ref "R2") (pin "1") (pintype "passive"))
    )
    (net (code "66") (name "Net-(J1-PadB5)") (class "Default")
      (node (ref "J1") (pin "B5") (pinfunction "B5_B5") (pintype "passive"))
      (node (ref "R3") (pin "1") (pintype "passive"))
    )
    (net (code "67") (name "Net-(U1-ADC_IOVDD)") (class "Default")
      (node (ref "C18") (pin "1") (pintype "passive"))
      (node (ref "C31") (pin "1") (pintype "passive"))
      (node (ref "R16") (pin "1") (pintype "passive"))
      (node (ref "U1") (pin "59") (pinfunction "ADC_IOVDD_59") (pintype "passive"))
    )
    (net (code "68") (name "Net-(U2-BST)") (class "Default")
      (node (ref "C30") (pin "2") (pintype "passive"))
      (node (ref "U2") (pin "6") (pinfunction "BST_6") (pintype "passive"))
    )
    (net (code "69") (name "Net-(U2-SW)") (class "Default")
      (node (ref "C30") (pin "1") (pintype "passive"))
      (node (ref "L1") (pin "1") (pinfunction "1_1") (pintype "passive"))
      (node (ref "U2") (pin "5") (pinfunction "SW_5") (pintype "passive"))
    )
    (net (code "70") (name "P3V3") (class "Default")
      (node (ref "C10") (pin "1") (pintype "passive"))
      (node (ref "C11") (pin "1") (pintype "passive"))
      (node (ref "C12") (pin "1") (pintype "passive"))
      (node (ref "C13") (pin "1") (pintype "passive"))
      (node (ref "C14") (pin "1") (pintype "passive"))
      (node (ref "C15") (pin "1") (pintype "passive"))
      (node (ref "C16") (pin "1") (pintype "passive"))
      (node (ref "C17") (pin "1") (pintype "passive"))
      (node (ref "C19") (pin "1") (pintype "passive"))
      (node (ref "C20") (pin "1") (pintype "passive"))
      (node (ref "C3") (pin "1") (pintype "passive"))
      (node (ref "C32") (pin "1") (pintype "passive"))
      (node (ref "C34") (pin "1") (pintype "passive"))
      (node (ref "C35") (pin "1") (pintype "passive"))
      (node (ref "C36") (pin "1") (pintype "passive"))
      (node (ref "C6") (pin "1") (pintype "passive"))
      (node (ref "C7") (pin "1") (pintype "passive"))
      (node (ref "C8") (pin "1") (pintype "passive"))
      (node (ref "C9") (pin "1") (pintype "passive"))
      (node (ref "J2") (pin "43") (pinfunction "P3V3_43") (pintype "passive"))
      (node (ref "R11") (pin "1") (pintype "passive"))
      (node (ref "R16") (pin "2") (pintype "passive"))
      (node (ref "R8") (pin "2") (pintype "passive"))
      (node (ref "R9") (pin "2") (pintype "passive"))
      (node (ref "U1") (pin "15") (pinfunction "IOVDD_15") (pintype "passive"))
      (node (ref "U1") (pin "24") (pinfunction "IOVDD_24") (pintype "passive"))
      (node (ref "U1") (pin "29") (pinfunction "IOVDD_29") (pintype "passive"))
      (node (ref "U1") (pin "41") (pinfunction "IOVDD_41") (pintype "passive"))
      (node (ref "U1") (pin "5") (pinfunction "IOVDD_5") (pintype "passive"))
      (node (ref "U1") (pin "50") (pinfunction "IOVDD_50") (pintype "passive"))
      (node (ref "U1") (pin "60") (pinfunction "IOVDD_60") (pintype "passive"))
      (node (ref "U1") (pin "68") (pinfunction "USBVDD_68") (pintype "passive"))
      (node (ref "U1") (pin "69") (pinfunction "QSPIVDD_69") (pintype "passive"))
      (node (ref "U1") (pin "76") (pinfunction "IOVDD_76") (pintype "passive"))
      (node (ref "U3") (pin "8") (pinfunction "VCC_8") (pintype "passive"))
      (node (ref "U4") (pin "1") (pinfunction "OE_1") (pintype "passive"))
      (node (ref "U4") (pin "4") (pinfunction "VCC_4") (pintype "passive"))
      (node (ref "U5") (pin "1") (pinfunction "IN_1") (pintype "passive"))
      (node (ref "U5") (pin "3") (pinfunction "EN_3") (pintype "passive"))
    )
    (net (code "71") (name "P3V3OUT") (class "Default")
      (node (ref "C21") (pin "1") (pintype "passive"))
      (node (ref "C4") (pin "1") (pintype "passive"))
      (node (ref "C5") (pin "1") (pintype "passive"))
      (node (ref "J2") (pin "41") (pinfunction "P3V3OUT_41") (pintype "passive"))
      (node (ref "L1") (pin "2") (pinfunction "2_2") (pintype "passive"))
      (node (ref "U2") (pin "1") (pinfunction "FB_1") (pintype "passive"))
    )
    (net (code "72") (name "RST") (class "Default")
      (node (ref "J2") (pin "42") (pinfunction "RST_42") (pintype "passive"))
      (node (ref "R9") (pin "1") (pintype "passive"))
      (node (ref "SW3") (pin "2") (pinfunction "2_2") (pintype "passive"))
      (node (ref "U1") (pin "35") (pinfunction "RUN_35") (pintype "passive"))
    )
    (net (code "73") (name "VBUS") (class "Default")
      (node (ref "J1") (pin "A4") (pinfunction "A4_A4") (pintype "passive"))
      (node (ref "J1") (pin "A9") (pinfunction "A9_A9") (pintype "passive"))
      (node (ref "J1") (pin "B4") (pinfunction "B4_B4") (pintype "passive"))
      (node (ref "J1") (pin "B9") (pinfunction "B9_B9") (pintype "passive"))
      (node (ref "J2") (pin "27") (pinfunction "VBUS_27") (pintype "passive"))
    )
    (net (code "74") (name "VSYS") (class "Default")
      (node (ref "C1") (pin "1") (pintype "passive"))
      (node (ref "C2") (pin "1") (pintype "passive"))
      (node (ref "C22") (pin "1") (pintype "passive"))
      (node (ref "J2") (pin "29") (pinfunction "VSYS_29") (pintype "passive"))
      (node (ref "U2") (pin "2") (pinfunction "EN_2") (pintype "passive"))
      (node (ref "U2") (pin "3") (pinfunction "VIN_3") (pintype "passive"))
    )
    (net (code "75") (name "unconnected-(J1-PadA8)") (class "Default")
      (node (ref "J1") (pin "A8") (pinfunction "A8_A8") (pintype "passive"))
    )
    (net (code "76") (name "unconnected-(J1-PadB8)") (class "Default")
      (node (ref "J1") (pin "B8") (pinfunction "B8_B8") (pintype "passive"))
    )
    (net (code "77") (name "unconnected-(SW2-Pad1)") (class "Default")
      (node (ref "SW2") (pin "1") (pinfunction "1_1") (pintype "passive"))
    )
    (net (code "78") (name "unconnected-(SW2-Pad3)") (class "Default")
      (node (ref "SW2") (pin "3") (pinfunction "3_3") (pintype "passive"))
    )
    (net (code "79") (name "unconnected-(SW3-Pad1)") (class "Default")
      (node (ref "SW3") (pin "1") (pinfunction "1_1") (pintype "passive"))
    )
    (net (code "80") (name "unconnected-(SW3-Pad3)") (class "Default")
      (node (ref "SW3") (pin "3") (pinfunction "3_3") (pintype "passive"))
    )
    (net (code "81") (name "unconnected-(U1-SWCLK-Pad33)") (class "Default")
      (node (ref "U1") (pin "33") (pinfunction "SWCLK_33") (pintype "passive"))
    )
    (net (code "82") (name "unconnected-(U1-SWD-Pad34)") (class "Default")
      (node (ref "U1") (pin "34") (pinfunction "SWD_34") (pintype "passive"))
    )
    (net (code "83") (name "unconnected-(U1-VREGFB-Pad65)") (class "Default")
      (node (ref "U1") (pin "65") (pinfunction "VREGFB_65") (pintype "passive"))
    )
    (net (code "84") (name "unconnected-(U1-VRLX-Pad63)") (class "Default")
      (node (ref "U1") (pin "63") (pinfunction "VRLX_63") (pintype "passive"))
    )
    (net (code "85") (name "unconnected-(U1-VRPGND-Pad62)") (class "Default")
      (node (ref "U1") (pin "62") (pinfunction "VRPGND_62") (pintype "passive"))
    )
    (net (code "86") (name "unconnected-(U1-XOUT-Pad31)") (class "Default")
      (node (ref "U1") (pin "31") (pinfunction "XOUT_31") (pintype "passive"))
    )
  )
)
